# anod_tap.net
KiCad netlist of a schematic drawn in EAGLE
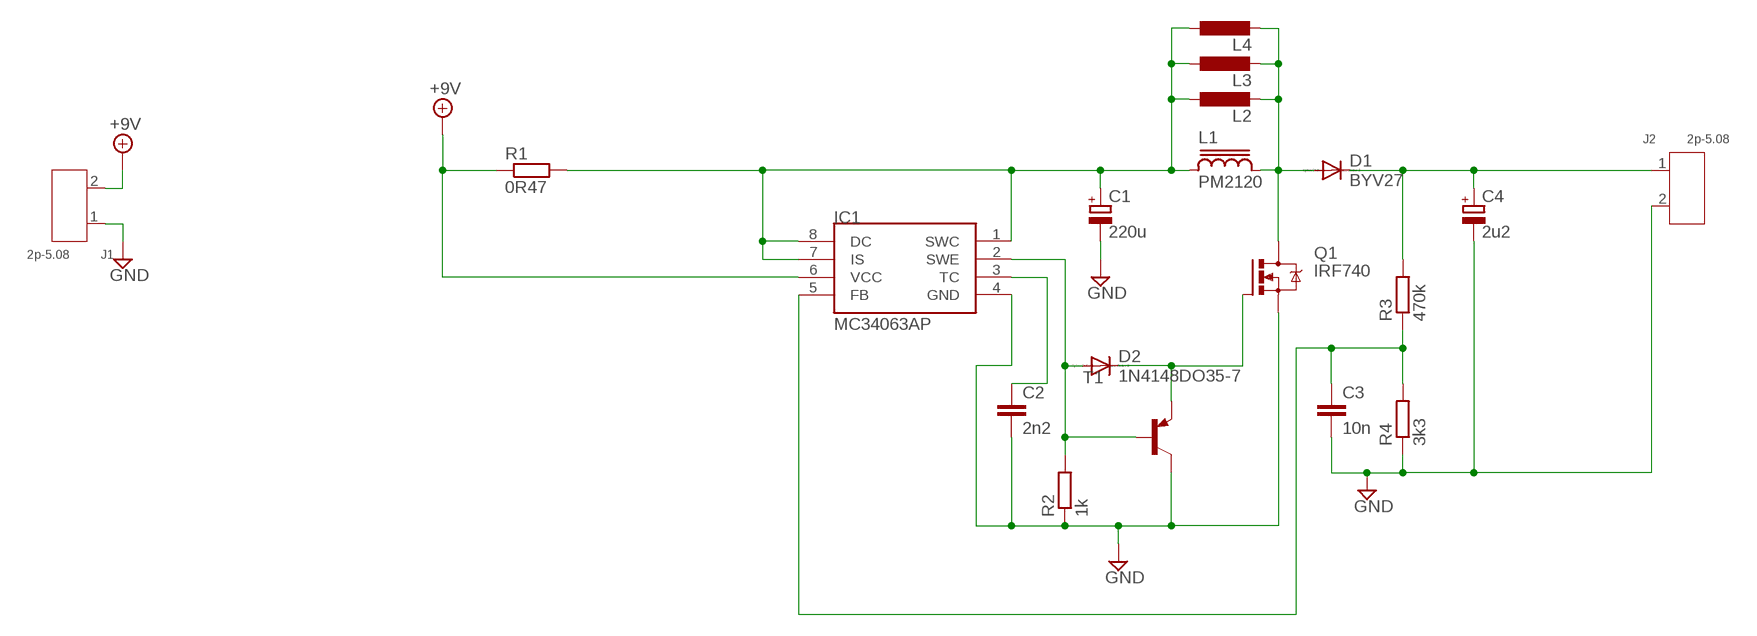
[diagram p0: schematic, sheet 1]

(export (version "E")
  (design (tool "Eeschema 10.0.6"))
  (components
    (comp (ref "C1")
      (value "220u")
      (footprint "eagle-import:E3,5-8")
      (libsource (lib "eagle-import") (part "CPOL-EUE3.5-8"))
    )
    (comp (ref "C2")
      (value "2n2")
      (footprint "eagle-import:C050-024X044")
      (libsource (lib "eagle-import") (part "C-EU050-024X044"))
    )
    (comp (ref "C3")
      (value "10n")
      (footprint "eagle-import:C050-024X044")
      (libsource (lib "eagle-import") (part "C-EU050-024X044"))
    )
    (comp (ref "C4")
      (value "2u2")
      (footprint "eagle-import:E3,5-8")
      (libsource (lib "eagle-import") (part "CPOL-EUE3.5-8"))
    )
    (comp (ref "D1")
      (value "BYV27")
      (footprint "eagle-import:SOD57-10")
      (libsource (lib "eagle-import") (part "BYV27"))
    )
    (comp (ref "D2")
      (value "1N4148DO35-7")
      (footprint "eagle-import:DO35-7")
      (libsource (lib "eagle-import") (part "1N4148DO35-7"))
    )
    (comp (ref "IC1")
      (value "MC34063AP")
      (footprint "eagle-import:DIL08")
      (libsource (lib "eagle-import") (part "MC34063AP"))
    )
    (comp (ref "J1")
      (value "2p-5.08")
      (footprint "eagle-import:H2-5.0-10.5X8.0MM")
      (fields (field (name "MPN") "GS009S-2P-2"))
      (libsource (lib "eagle-import") (part "DIP-BLUE-SCREW-TERMINAL(2P-5.08)"))
    )
    (comp (ref "J2")
      (value "2p-5.08")
      (footprint "eagle-import:H2-5.0-10.5X8.0MM")
      (fields (field (name "MPN") "GS009S-2P-2"))
      (libsource (lib "eagle-import") (part "DIP-BLUE-SCREW-TERMINAL(2P-5.08)"))
    )
    (comp (ref "L1")
      (value "PM2120")
      (footprint "eagle-import:PM2120")
      (libsource (lib "eagle-import") (part "PM2120"))
    )
    (comp (ref "L2")
      (value "L-EUTJ3-U1")
      (footprint "eagle-import:TJ3-U1")
      (libsource (lib "eagle-import") (part "L-EUTJ3-U1"))
    )
    (comp (ref "L3")
      (value "L-EUTJ3-U2")
      (footprint "eagle-import:TJ3-U2")
      (libsource (lib "eagle-import") (part "L-EUTJ3-U2"))
    )
    (comp (ref "L4")
      (value "L-EUTJ4-U2")
      (footprint "eagle-import:TJ4-U2")
      (libsource (lib "eagle-import") (part "L-EUTJ4-U2"))
    )
    (comp (ref "Q1")
      (value "IRF740")
      (footprint "eagle-import:TO220BV")
      (libsource (lib "eagle-import") (part "IRF740"))
    )
    (comp (ref "R1")
      (value "0R47")
      (footprint "eagle-import:0922_22")
      (libsource (lib "eagle-import") (part "R-EU_0922/22"))
    )
    (comp (ref "R2")
      (value "1k")
      (footprint "eagle-import:0204_5")
      (libsource (lib "eagle-import") (part "R-EU_0204/5"))
    )
    (comp (ref "R3")
      (value "470k")
      (footprint "eagle-import:0204_5")
      (libsource (lib "eagle-import") (part "R-EU_0204/5"))
    )
    (comp (ref "R4")
      (value "3k3")
      (footprint "eagle-import:0204_5")
      (libsource (lib "eagle-import") (part "R-EU_0204/5"))
    )
    (comp (ref "T1")
      (value "MPSA92-PNP-TO92-EBC")
      (footprint "eagle-import:TO92-EBC")
      (libsource (lib "eagle-import") (part "-PNP-TO92-EBCMPSA92"))
    )
  )
  (nets
    (net (code "1") (name "+9V") (class "Default")
      (node (ref "IC1") (pin "6") (pinfunction "VCC_6") (pintype "passive"))
      (node (ref "J1") (pin "2") (pinfunction "2_2") (pintype "bidirectional"))
      (node (ref "R1") (pin "1") (pinfunction "1_1") (pintype "passive"))
    )
    (net (code "2") (name "GND") (class "Default")
      (node (ref "C1") (pin "-") (pinfunction "-_-") (pintype "passive"))
      (node (ref "C2") (pin "2") (pinfunction "2_2") (pintype "passive"))
      (node (ref "C3") (pin "2") (pinfunction "2_2") (pintype "passive"))
      (node (ref "C4") (pin "-") (pinfunction "-_-") (pintype "passive"))
      (node (ref "IC1") (pin "4") (pinfunction "GND_4") (pintype "passive"))
      (node (ref "J1") (pin "1") (pinfunction "1_1") (pintype "bidirectional"))
      (node (ref "J2") (pin "2") (pinfunction "2_2") (pintype "bidirectional"))
      (node (ref "Q1") (pin "S") (pinfunction "S_S") (pintype "passive"))
      (node (ref "R2") (pin "1") (pinfunction "1_1") (pintype "passive"))
      (node (ref "R4") (pin "1") (pinfunction "1_1") (pintype "passive"))
      (node (ref "T1") (pin "C") (pinfunction "C_C") (pintype "passive"))
    )
    (net (code "3") (name "Net-(C4-Pad+)") (class "Default")
      (node (ref "C4") (pin "+") (pinfunction "+_+") (pintype "passive"))
      (node (ref "D1") (pin "C") (pinfunction "C_C") (pintype "passive"))
      (node (ref "J2") (pin "1") (pinfunction "1_1") (pintype "bidirectional"))
      (node (ref "R3") (pin "2") (pinfunction "2_2") (pintype "passive"))
    )
    (net (code "4") (name "Net-(D1-PadA)") (class "Default")
      (node (ref "D1") (pin "A") (pinfunction "A_A") (pintype "passive"))
      (node (ref "L1") (pin "2") (pinfunction "2_2") (pintype "passive"))
      (node (ref "L2") (pin "2") (pinfunction "2_2") (pintype "passive"))
      (node (ref "L3") (pin "2") (pinfunction "2_2") (pintype "passive"))
      (node (ref "L4") (pin "2") (pinfunction "2_2") (pintype "passive"))
      (node (ref "Q1") (pin "D") (pinfunction "D_D") (pintype "passive"))
    )
    (net (code "5") (name "Net-(D2-PadC)") (class "Default")
      (node (ref "D2") (pin "C") (pinfunction "C_C") (pintype "passive"))
      (node (ref "Q1") (pin "G") (pinfunction "G_G") (pintype "passive"))
      (node (ref "T1") (pin "E") (pinfunction "E_E") (pintype "passive"))
    )
    (net (code "6") (name "Net-(IC1-DC)") (class "Default")
      (node (ref "C1") (pin "+") (pinfunction "+_+") (pintype "passive"))
      (node (ref "IC1") (pin "1") (pinfunction "SWC_1") (pintype "passive"))
      (node (ref "IC1") (pin "7") (pinfunction "IS_7") (pintype "passive"))
      (node (ref "IC1") (pin "8") (pinfunction "DC_8") (pintype "passive"))
      (node (ref "L1") (pin "1") (pinfunction "1_1") (pintype "passive"))
      (node (ref "L2") (pin "1") (pinfunction "1_1") (pintype "passive"))
      (node (ref "L3") (pin "1") (pinfunction "1_1") (pintype "passive"))
      (node (ref "L4") (pin "1") (pinfunction "1_1") (pintype "passive"))
      (node (ref "R1") (pin "2") (pinfunction "2_2") (pintype "passive"))
    )
    (net (code "7") (name "Net-(IC1-FB)") (class "Default")
      (node (ref "C3") (pin "1") (pinfunction "1_1") (pintype "passive"))
      (node (ref "IC1") (pin "5") (pinfunction "FB_5") (pintype "passive"))
      (node (ref "R3") (pin "1") (pinfunction "1_1") (pintype "passive"))
      (node (ref "R4") (pin "2") (pinfunction "2_2") (pintype "passive"))
    )
    (net (code "8") (name "Net-(IC1-SWE)") (class "Default")
      (node (ref "D2") (pin "A") (pinfunction "A_A") (pintype "passive"))
      (node (ref "IC1") (pin "2") (pinfunction "SWE_2") (pintype "passive"))
      (node (ref "R2") (pin "2") (pinfunction "2_2") (pintype "passive"))
      (node (ref "T1") (pin "B") (pinfunction "B_B") (pintype "passive"))
    )
    (net (code "9") (name "Net-(IC1-TC)") (class "Default")
      (node (ref "C2") (pin "1") (pinfunction "1_1") (pintype "passive"))
      (node (ref "IC1") (pin "3") (pinfunction "TC_3") (pintype "passive"))
    )
  )
)
